# blink1mk3_micro1e.net
KiCad netlist of a schematic drawn in EAGLE
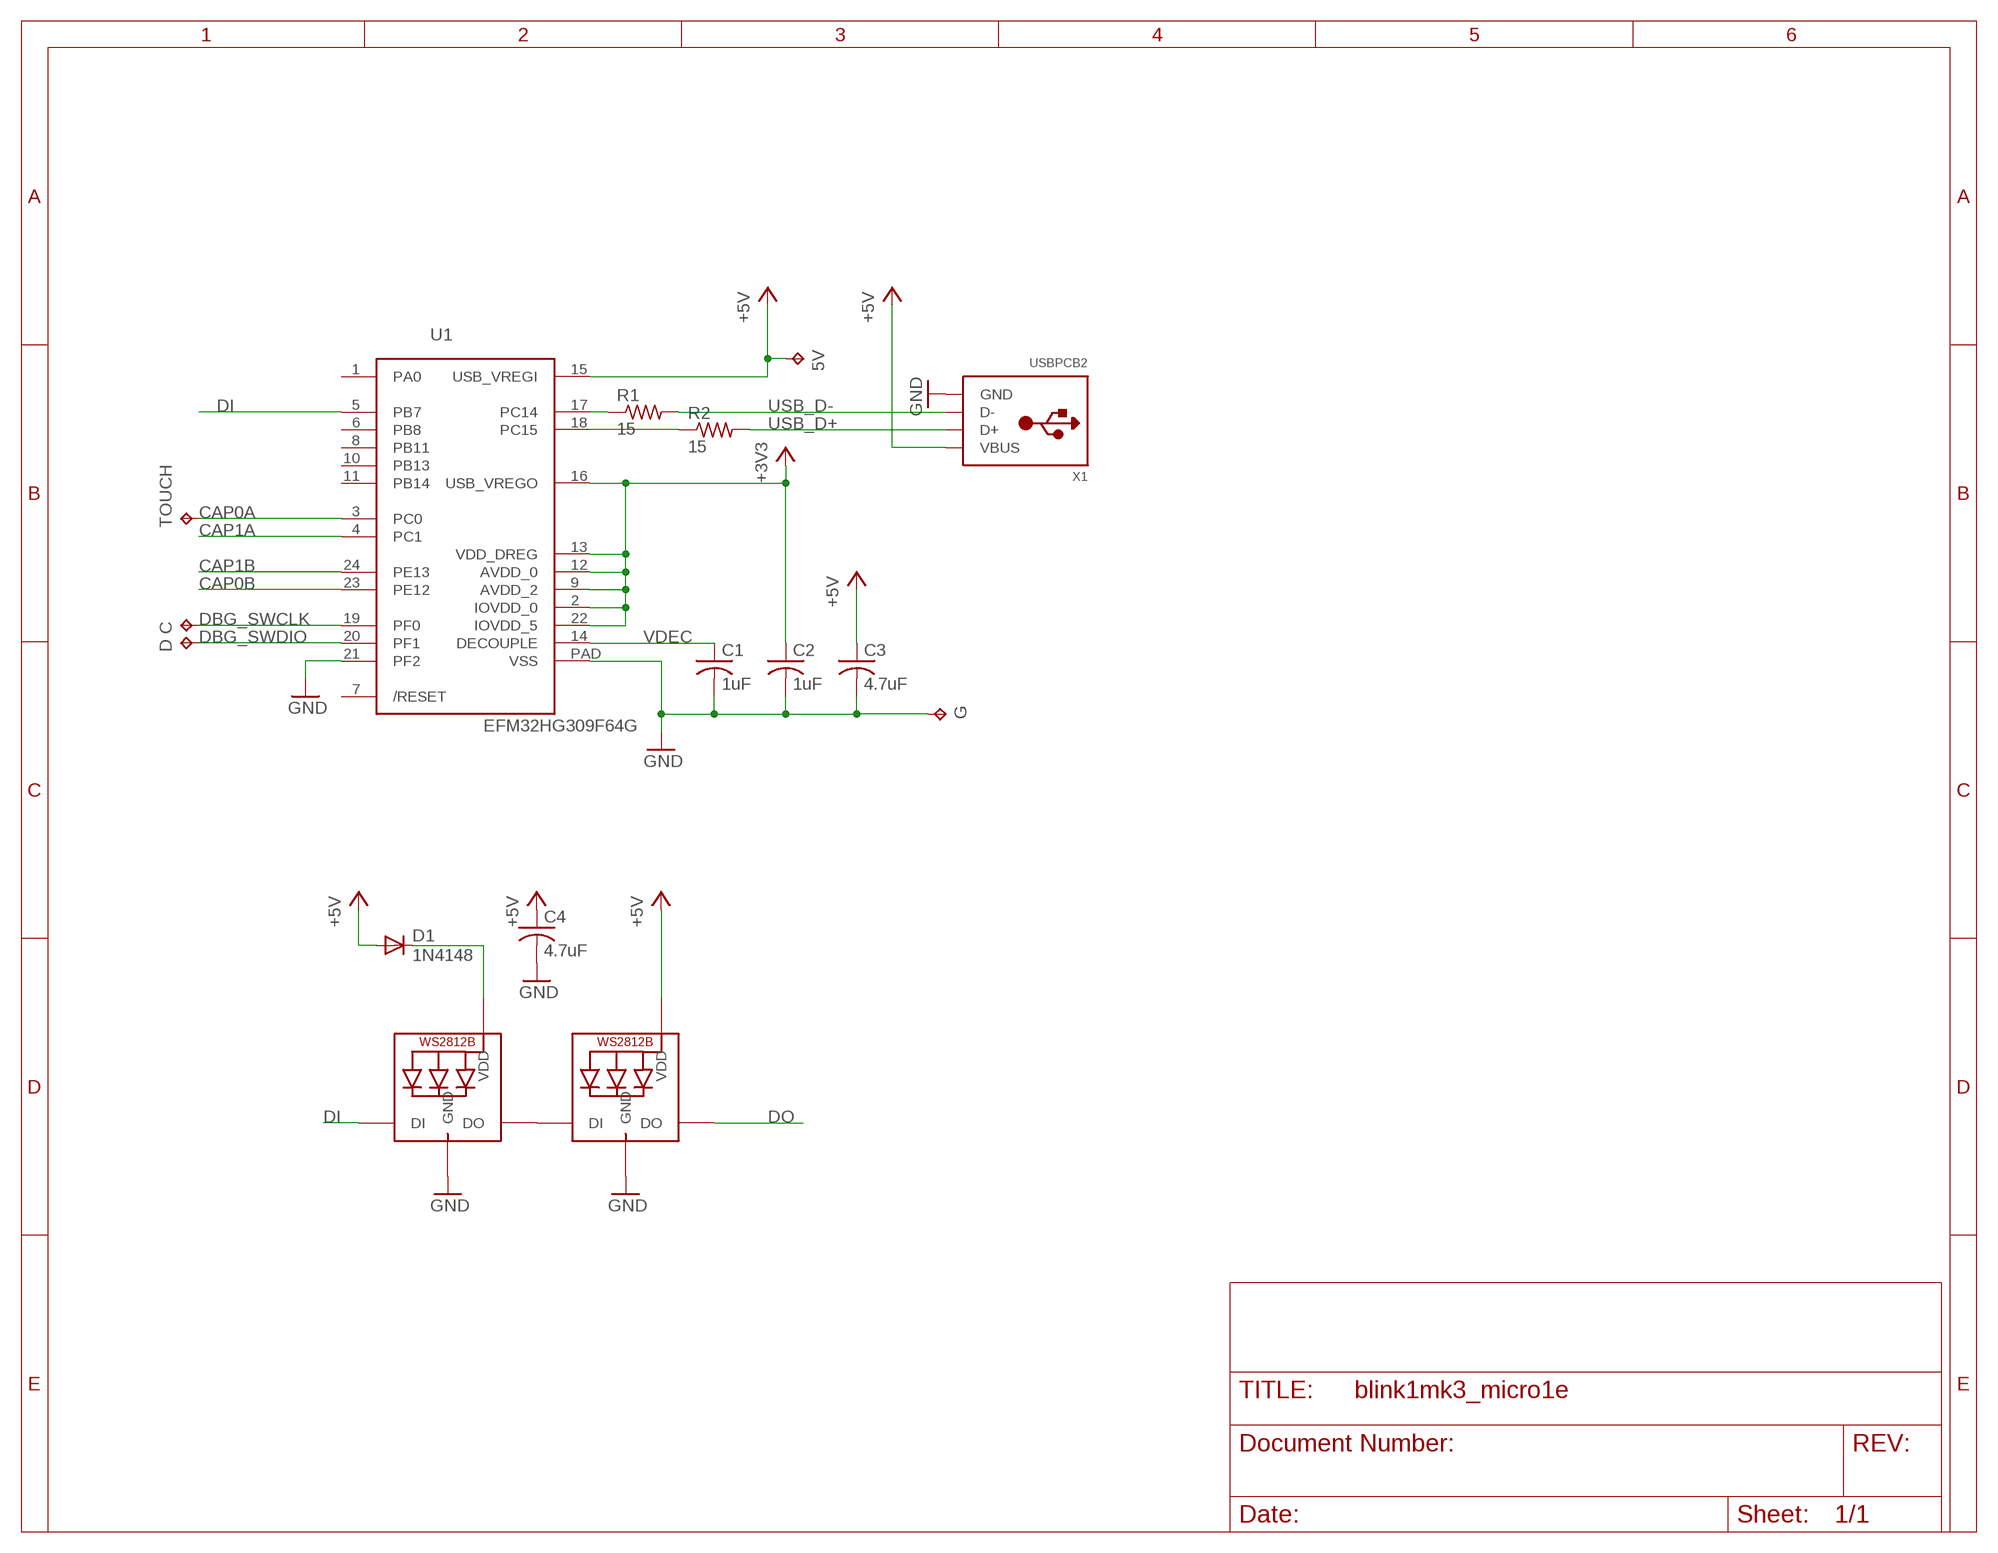
[diagram p0: schematic, sheet 1]

(export (version "E")
  (design (tool "Eeschema 10.0.6"))
  (components
    (comp (ref "5V")
      (value "TPTP10R")
      (footprint "eagle-import:TP10R")
      (libsource (lib "eagle-import") (part "TPTP10R"))
    )
    (comp (ref "C")
      (value "TPTP10R")
      (footprint "eagle-import:TP10R")
      (libsource (lib "eagle-import") (part "TPTP10R"))
    )
    (comp (ref "C1")
      (value "1uF")
      (footprint "eagle-import:C0402")
      (libsource (lib "eagle-import") (part "C-USC0402"))
    )
    (comp (ref "C2")
      (value "1uF")
      (footprint "eagle-import:C0402")
      (libsource (lib "eagle-import") (part "C-USC0402"))
    )
    (comp (ref "C3")
      (value "4.7uF")
      (footprint "eagle-import:C0402")
      (libsource (lib "eagle-import") (part "C-USC0402"))
    )
    (comp (ref "C4")
      (value "4.7uF")
      (footprint "eagle-import:C0402")
      (libsource (lib "eagle-import") (part "C-USC0402"))
    )
    (comp (ref "D")
      (value "TPTP10R")
      (footprint "eagle-import:TP10R")
      (libsource (lib "eagle-import") (part "TPTP10R"))
    )
    (comp (ref "D1")
      (value "1N4148")
      (footprint "eagle-import:SOD523")
      (libsource (lib "eagle-import") (part "DIODE-SOD523"))
    )
    (comp (ref "G")
      (value "TPTP10SQ")
      (footprint "eagle-import:TP10SQ")
      (libsource (lib "eagle-import") (part "TPTP10SQ"))
    )
    (comp (ref "LED1")
      (value "WS2812B4020SIDE")
      (footprint "eagle-import:SK6812-SIDE")
      (libsource (lib "eagle-import") (part "WS2812B4020SIDE"))
    )
    (comp (ref "LED2")
      (value "WS2812B4020SIDE")
      (footprint "eagle-import:SK6812-SIDE")
      (libsource (lib "eagle-import") (part "WS2812B4020SIDE"))
    )
    (comp (ref "R1")
      (value "15")
      (footprint "eagle-import:R0402")
      (libsource (lib "eagle-import") (part "R-US_R0402"))
    )
    (comp (ref "R2")
      (value "15")
      (footprint "eagle-import:R0402")
      (libsource (lib "eagle-import") (part "R-US_R0402"))
    )
    (comp (ref "TOUCH")
      (value "TPTP10R")
      (footprint "eagle-import:TP10R")
      (libsource (lib "eagle-import") (part "TPTP10R"))
    )
    (comp (ref "U1")
      (value "EFM32HG309F64G")
      (footprint "eagle-import:QFN24PAD")
      (libsource (lib "eagle-import") (part "EFM32HG309F64G"))
    )
    (comp (ref "X1")
      (value "USBPCB2")
      (footprint "eagle-import:USB-A-PCB-2")
      (libsource (lib "eagle-import") (part "USBPCB2"))
    )
  )
  (nets
    (net (code "1") (name "+3V3") (class "Default")
      (node (ref "C2") (pin "1") (pinfunction "1_1") (pintype "passive"))
      (node (ref "U1") (pin "12") (pinfunction "AVDD_0_12") (pintype "bidirectional"))
      (node (ref "U1") (pin "13") (pinfunction "VDD_DREG_13") (pintype "bidirectional"))
      (node (ref "U1") (pin "16") (pinfunction "USB_VREGO_16") (pintype "bidirectional"))
      (node (ref "U1") (pin "2") (pinfunction "IOVDD_0_2") (pintype "bidirectional"))
      (node (ref "U1") (pin "22") (pinfunction "IOVDD_5_22") (pintype "bidirectional"))
      (node (ref "U1") (pin "9") (pinfunction "AVDD_2_9") (pintype "bidirectional"))
    )
    (net (code "2") (name "+5V") (class "Default")
      (node (ref "5V") (pin "TP") (pinfunction "TP_TP") (pintype "input"))
      (node (ref "C3") (pin "1") (pinfunction "1_1") (pintype "passive"))
      (node (ref "C4") (pin "1") (pinfunction "1_1") (pintype "passive"))
      (node (ref "D1") (pin "A") (pinfunction "A_A") (pintype "passive"))
      (node (ref "LED2") (pin "1-VDD") (pinfunction "VDD_1-VDD") (pintype "power_in"))
      (node (ref "U1") (pin "15") (pinfunction "USB_VREGI_15") (pintype "bidirectional"))
      (node (ref "X1") (pin "5V") (pinfunction "VBUS_5V") (pintype "power_in"))
    )
    (net (code "3") (name "/CAP0A") (class "Default")
      (node (ref "TOUCH") (pin "TP") (pinfunction "TP_TP") (pintype "input"))
      (node (ref "U1") (pin "3") (pinfunction "PC0_3") (pintype "bidirectional"))
    )
    (net (code "4") (name "/CAP0B") (class "Default")
      (node (ref "U1") (pin "23") (pinfunction "PE12_23") (pintype "bidirectional"))
    )
    (net (code "5") (name "/CAP1A") (class "Default")
      (node (ref "U1") (pin "4") (pinfunction "PC1_4") (pintype "bidirectional"))
    )
    (net (code "6") (name "/CAP1B") (class "Default")
      (node (ref "U1") (pin "24") (pinfunction "PE13_24") (pintype "bidirectional"))
    )
    (net (code "7") (name "/DBG_SWCLK") (class "Default")
      (node (ref "C") (pin "TP") (pinfunction "TP_TP") (pintype "input"))
      (node (ref "U1") (pin "19") (pinfunction "PF0_19") (pintype "bidirectional"))
    )
    (net (code "8") (name "/DBG_SWDIO") (class "Default")
      (node (ref "D") (pin "TP") (pinfunction "TP_TP") (pintype "input"))
      (node (ref "U1") (pin "20") (pinfunction "PF1_20") (pintype "bidirectional"))
    )
    (net (code "9") (name "/DI") (class "Default")
      (node (ref "LED1") (pin "4-DIN") (pinfunction "DI_4-DIN") (pintype "input"))
      (node (ref "U1") (pin "5") (pinfunction "PB7_5") (pintype "bidirectional"))
    )
    (net (code "10") (name "/DO") (class "Default")
      (node (ref "LED2") (pin "2-DOUT") (pinfunction "DO_2-DOUT") (pintype "output"))
    )
    (net (code "11") (name "/USB_D+") (class "Default")
      (node (ref "R2") (pin "2") (pinfunction "2_2") (pintype "passive"))
      (node (ref "X1") (pin "USB_P") (pinfunction "D+_USB_P") (pintype "bidirectional"))
    )
    (net (code "12") (name "/USB_D-") (class "Default")
      (node (ref "R1") (pin "2") (pinfunction "2_2") (pintype "passive"))
      (node (ref "X1") (pin "USB_M") (pinfunction "D-_USB_M") (pintype "bidirectional"))
    )
    (net (code "13") (name "/VDEC") (class "Default")
      (node (ref "C1") (pin "1") (pinfunction "1_1") (pintype "passive"))
      (node (ref "U1") (pin "14") (pinfunction "DECOUPLE_14") (pintype "bidirectional"))
    )
    (net (code "14") (name "GND") (class "Default")
      (node (ref "C1") (pin "2") (pinfunction "2_2") (pintype "passive"))
      (node (ref "C2") (pin "2") (pinfunction "2_2") (pintype "passive"))
      (node (ref "C3") (pin "2") (pinfunction "2_2") (pintype "passive"))
      (node (ref "C4") (pin "2") (pinfunction "2_2") (pintype "passive"))
      (node (ref "G") (pin "TP") (pinfunction "TP_TP") (pintype "input"))
      (node (ref "LED1") (pin "3-GND") (pinfunction "GND_3-GND") (pintype "power_in"))
      (node (ref "LED2") (pin "3-GND") (pinfunction "GND_3-GND") (pintype "power_in"))
      (node (ref "U1") (pin "21") (pinfunction "PF2_21") (pintype "bidirectional"))
      (node (ref "U1") (pin "PAD") (pinfunction "VSS_PAD") (pintype "bidirectional"))
      (node (ref "X1") (pin "GND") (pinfunction "GND_GND") (pintype "power_in"))
    )
    (net (code "15") (name "Net-(LED1-DO)") (class "Default")
      (node (ref "LED1") (pin "2-DOUT") (pinfunction "DO_2-DOUT") (pintype "output"))
      (node (ref "LED2") (pin "4-DIN") (pinfunction "DI_4-DIN") (pintype "input"))
    )
    (net (code "16") (name "Net-(LED1-VDD)") (class "Default")
      (node (ref "D1") (pin "C") (pinfunction "C_C") (pintype "passive"))
      (node (ref "LED1") (pin "1-VDD") (pinfunction "VDD_1-VDD") (pintype "power_in"))
    )
    (net (code "17") (name "Net-(U1-PC14)") (class "Default")
      (node (ref "R1") (pin "1") (pinfunction "1_1") (pintype "passive"))
      (node (ref "U1") (pin "17") (pinfunction "PC14_17") (pintype "bidirectional"))
    )
    (net (code "18") (name "Net-(U1-PC15)") (class "Default")
      (node (ref "R2") (pin "1") (pinfunction "1_1") (pintype "passive"))
      (node (ref "U1") (pin "18") (pinfunction "PC15_18") (pintype "bidirectional"))
    )
    (net (code "19") (name "unconnected-(U1-PA0-Pad1)") (class "Default")
      (node (ref "U1") (pin "1") (pinfunction "PA0_1") (pintype "bidirectional"))
    )
    (net (code "20") (name "unconnected-(U1-PB8-Pad6)") (class "Default")
      (node (ref "U1") (pin "6") (pinfunction "PB8_6") (pintype "bidirectional"))
    )
    (net (code "21") (name "unconnected-(U1-PB11-Pad8)") (class "Default")
      (node (ref "U1") (pin "8") (pinfunction "PB11_8") (pintype "bidirectional"))
    )
    (net (code "22") (name "unconnected-(U1-PB13-Pad10)") (class "Default")
      (node (ref "U1") (pin "10") (pinfunction "PB13_10") (pintype "bidirectional"))
    )
    (net (code "23") (name "unconnected-(U1-PB14-Pad11)") (class "Default")
      (node (ref "U1") (pin "11") (pinfunction "PB14_11") (pintype "bidirectional"))
    )
    (net (code "24") (name "unconnected-(U1-{slash}RESET-Pad7)") (class "Default")
      (node (ref "U1") (pin "7") (pinfunction "/RESET_7") (pintype "bidirectional"))
    )
  )
)
